# Main.net
KiCad netlist of a schematic drawn in Altium Designer
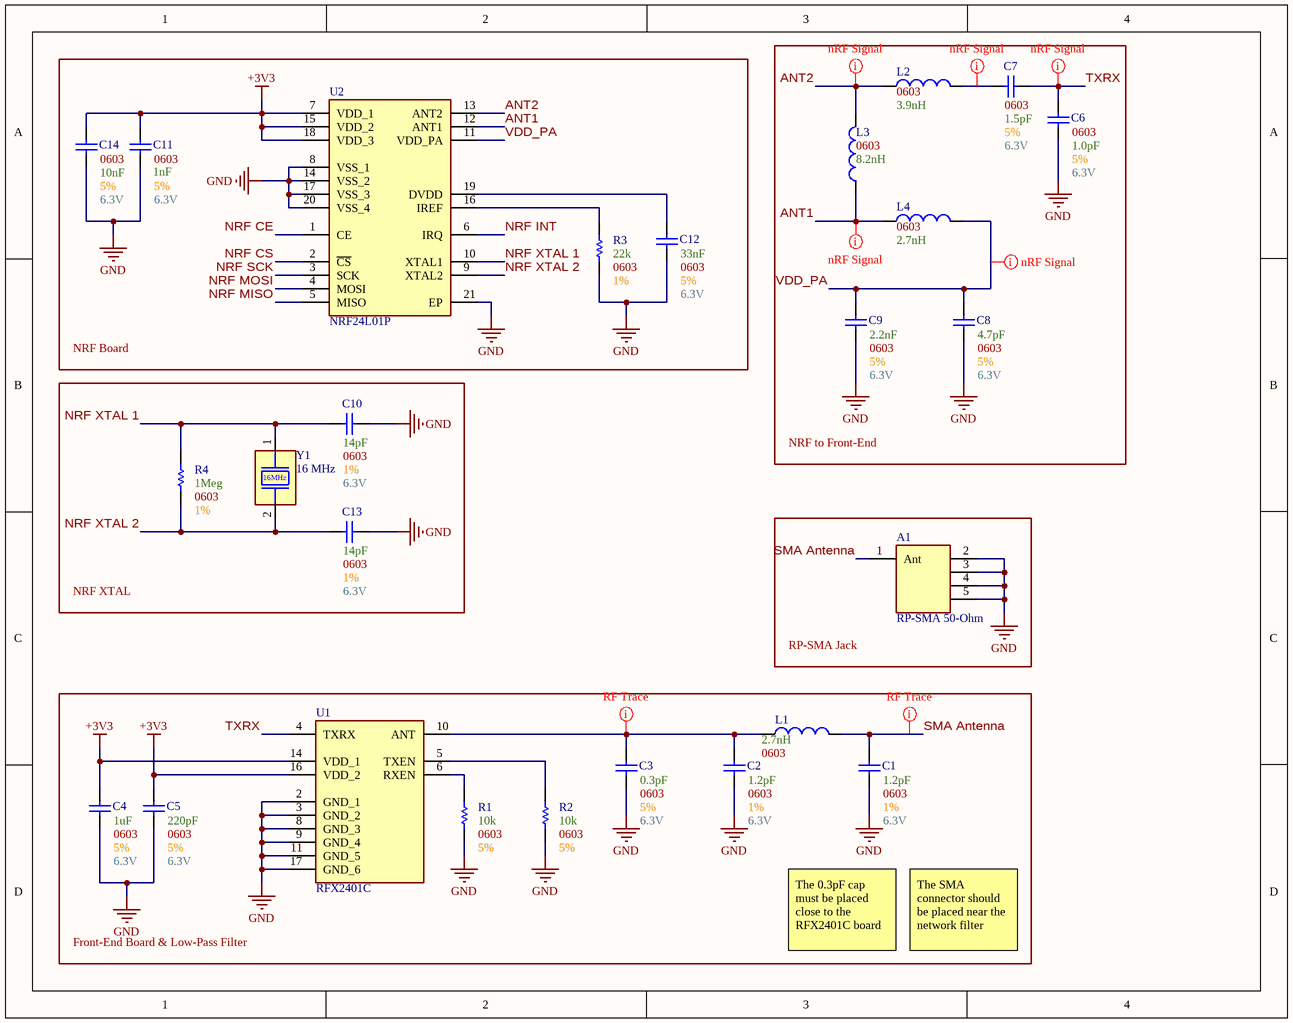
[diagram p0: Main.SchDoc]

(export (version "E")
  (design (tool "Eeschema 10.0.6"))
  (components
    (comp (ref "A1")
      (value "RP-SMA 50-Ohm")
      (footprint "[SMA] RP-SMA 90deg Jack")
      (description "PCB.RPSMAFRA.HT")
      (libsource (lib "RADM Connectors") (part "[SMA] RP-SMA 90deg Jack"))
    )
    (comp (ref "C1")
      (value "SMD Nonpolarized")
      (footprint "[Cap] SMD 0603")
      (fields
        (field (name "VOLTAGE") "6.3V")
        (field (name "TOLERANCE") "1%")
        (field (name "SIZE PACKAGE") "0603")
        (field (name "CAPACITANCE") "1.2pF")
      )
      (libsource (lib "RADM Components") (part "[Cap] SMD Nonpolarized"))
    )
    (comp (ref "C2")
      (value "SMD Nonpolarized")
      (footprint "[Cap] SMD 0603")
      (fields
        (field (name "VOLTAGE") "6.3V")
        (field (name "TOLERANCE") "1%")
        (field (name "SIZE PACKAGE") "0603")
        (field (name "CAPACITANCE") "1.2pF")
      )
      (libsource (lib "RADM Components") (part "[Cap] SMD Nonpolarized"))
    )
    (comp (ref "C3")
      (value "SMD Nonpolarized")
      (footprint "[Cap] SMD 0603")
      (fields
        (field (name "TOLERANCE") "5%")
        (field (name "SIZE PACKAGE") "0603")
        (field (name "CAPACITANCE") "0.3pF")
        (field (name "VOLTAGE") "6.3V")
      )
      (libsource (lib "RADM Components") (part "[Cap] SMD Nonpolarized"))
    )
    (comp (ref "C4")
      (value "SMD Nonpolarized")
      (footprint "[Cap] SMD 0603")
      (fields
        (field (name "TOLERANCE") "5%")
        (field (name "SIZE PACKAGE") "0603")
        (field (name "CAPACITANCE") "1uF")
        (field (name "VOLTAGE") "6.3V")
      )
      (libsource (lib "RADM Components") (part "[Cap] SMD Nonpolarized"))
    )
    (comp (ref "C5")
      (value "SMD Nonpolarized")
      (footprint "[Cap] SMD 0603")
      (fields
        (field (name "TOLERANCE") "5%")
        (field (name "SIZE PACKAGE") "0603")
        (field (name "CAPACITANCE") "220pF")
        (field (name "VOLTAGE") "6.3V")
      )
      (libsource (lib "RADM Components") (part "[Cap] SMD Nonpolarized"))
    )
    (comp (ref "C6")
      (value "SMD Nonpolarized")
      (footprint "[Cap] SMD 0603")
      (fields
        (field (name "TOLERANCE") "5%")
        (field (name "SIZE PACKAGE") "0603")
        (field (name "CAPACITANCE") "1.0pF")
        (field (name "VOLTAGE") "6.3V")
      )
      (libsource (lib "RADM Components") (part "[Cap] SMD Nonpolarized"))
    )
    (comp (ref "C7")
      (value "SMD Nonpolarized")
      (footprint "[Cap] SMD 0603")
      (fields
        (field (name "TOLERANCE") "5%")
        (field (name "SIZE PACKAGE") "0603")
        (field (name "CAPACITANCE") "1.5pF")
        (field (name "VOLTAGE") "6.3V")
      )
      (libsource (lib "RADM Components") (part "[Cap] SMD Nonpolarized"))
    )
    (comp (ref "C8")
      (value "SMD Nonpolarized")
      (footprint "[Cap] SMD 0603")
      (fields
        (field (name "TOLERANCE") "5%")
        (field (name "SIZE PACKAGE") "0603")
        (field (name "CAPACITANCE") "4.7pF")
        (field (name "VOLTAGE") "6.3V")
      )
      (libsource (lib "RADM Components") (part "[Cap] SMD Nonpolarized"))
    )
    (comp (ref "C9")
      (value "SMD Nonpolarized")
      (footprint "[Cap] SMD 0603")
      (fields
        (field (name "TOLERANCE") "5%")
        (field (name "SIZE PACKAGE") "0603")
        (field (name "CAPACITANCE") "2.2nF")
        (field (name "VOLTAGE") "6.3V")
      )
      (libsource (lib "RADM Components") (part "[Cap] SMD Nonpolarized"))
    )
    (comp (ref "C10")
      (value "SMD Nonpolarized")
      (footprint "[Cap] SMD 0603")
      (fields
        (field (name "TOLERANCE") "1%")
        (field (name "SIZE PACKAGE") "0603")
        (field (name "CAPACITANCE") "14pF")
        (field (name "VOLTAGE") "6.3V")
      )
      (libsource (lib "RADM Components") (part "[Cap] SMD Nonpolarized"))
    )
    (comp (ref "C11")
      (value "SMD Nonpolarized")
      (footprint "[Cap] SMD 0603")
      (fields
        (field (name "TOLERANCE") "5%")
        (field (name "SIZE PACKAGE") "0603")
        (field (name "CAPACITANCE") "1nF")
        (field (name "VOLTAGE") "6.3V")
      )
      (libsource (lib "RADM Components") (part "[Cap] SMD Nonpolarized"))
    )
    (comp (ref "C12")
      (value "SMD Nonpolarized")
      (footprint "[Cap] SMD 0603")
      (fields
        (field (name "TOLERANCE") "5%")
        (field (name "SIZE PACKAGE") "0603")
        (field (name "CAPACITANCE") "33nF")
        (field (name "VOLTAGE") "6.3V")
      )
      (libsource (lib "RADM Components") (part "[Cap] SMD Nonpolarized"))
    )
    (comp (ref "C13")
      (value "SMD Nonpolarized")
      (footprint "[Cap] SMD 0603")
      (fields
        (field (name "TOLERANCE") "1%")
        (field (name "SIZE PACKAGE") "0603")
        (field (name "CAPACITANCE") "14pF")
        (field (name "VOLTAGE") "6.3V")
      )
      (libsource (lib "RADM Components") (part "[Cap] SMD Nonpolarized"))
    )
    (comp (ref "C14")
      (value "SMD Nonpolarized")
      (footprint "[Cap] SMD 0603")
      (fields
        (field (name "TOLERANCE") "5%")
        (field (name "SIZE PACKAGE") "0603")
        (field (name "CAPACITANCE") "10nF")
        (field (name "VOLTAGE") "6.3V")
      )
      (libsource (lib "RADM Components") (part "[Cap] SMD Nonpolarized"))
    )
    (comp (ref "L1")
      (value "SMD Inductor")
      (footprint "[Inductor] SMD 0603")
      (fields (field (name "SIZE PACKAGE") "0603") (field (name "INDUCTANCE") "2.7nH"))
      (libsource (lib "RADM Components") (part "[Inductor] SMD Inductor"))
    )
    (comp (ref "L2")
      (value "SMD Inductor")
      (footprint "[Inductor] SMD 0603")
      (fields (field (name "SIZE PACKAGE") "0603") (field (name "INDUCTANCE") "3.9nH"))
      (libsource (lib "RADM Components") (part "[Inductor] SMD Inductor"))
    )
    (comp (ref "L3")
      (value "SMD Inductor")
      (footprint "[Inductor] SMD 0603")
      (fields (field (name "SIZE PACKAGE") "0603") (field (name "INDUCTANCE") "8.2nH"))
      (libsource (lib "RADM Components") (part "[Inductor] SMD Inductor"))
    )
    (comp (ref "L4")
      (value "SMD Inductor")
      (footprint "[Inductor] SMD 0603")
      (fields (field (name "SIZE PACKAGE") "0603") (field (name "INDUCTANCE") "2.7nH"))
      (libsource (lib "RADM Components") (part "[Inductor] SMD Inductor"))
    )
    (comp (ref "R1")
      (value "[Res] SMD Resistor")
      (footprint "[Res] SMD 0603")
      (description "Generic")
      (fields
        (field (name "TOLERANCE") "5%")
        (field (name "RESISTANCE") "10k")
        (field (name "SIZE PACKAGE") "0603")
      )
      (libsource (lib "RADM Components") (part "[Res] SMD Resistor"))
    )
    (comp (ref "R2")
      (value "[Res] SMD Resistor")
      (footprint "[Res] SMD 0603")
      (description "Generic")
      (fields
        (field (name "TOLERANCE") "5%")
        (field (name "RESISTANCE") "10k")
        (field (name "SIZE PACKAGE") "0603")
      )
      (libsource (lib "RADM Components") (part "[Res] SMD Resistor"))
    )
    (comp (ref "R3")
      (value "[Res] SMD Resistor")
      (footprint "[Res] SMD 0603")
      (description "Generic")
      (fields
        (field (name "TOLERANCE") "1%")
        (field (name "RESISTANCE") "22k")
        (field (name "SIZE PACKAGE") "0603")
      )
      (libsource (lib "RADM Components") (part "[Res] SMD Resistor"))
    )
    (comp (ref "R4")
      (value "[Res] SMD Resistor")
      (footprint "[Res] SMD 0603")
      (description "Generic")
      (fields
        (field (name "TOLERANCE") "1%")
        (field (name "RESISTANCE") "1Meg")
        (field (name "SIZE PACKAGE") "0603")
      )
      (libsource (lib "RADM Components") (part "[Res] SMD Resistor"))
    )
    (comp (ref "U1")
      (value "RFX2401C")
      (footprint "[IC] RF Front-End")
      (libsource (lib "RADM Components") (part "[IC] RF Front-End"))
    )
    (comp (ref "U2")
      (value "NRF24L01P")
      (footprint "[IC] NRF Transceiver")
      (description "NRF24L01P-R")
      (libsource (lib "RADM Components") (part "[IC] NRF Transceiver"))
    )
    (comp (ref "Y1")
      (value "16 MHz")
      (footprint "[XTAL] SMD 16MHz (2)")
      (description "ABM11-16.000MHZ-12-N1G-T")
      (libsource (lib "RADM Components") (part "[XTAL] SMD 16MHz (2)"))
    )
  )
  (nets
    (net (code "1") (name "+3V3") (class "Default")
      (node (ref "C11") (pin "2") (pinfunction "2_2") (pintype "passive"))
      (node (ref "C14") (pin "2") (pinfunction "2_2") (pintype "passive"))
      (node (ref "C4") (pin "2") (pinfunction "2_2") (pintype "passive"))
      (node (ref "C5") (pin "2") (pinfunction "2_2") (pintype "passive"))
      (node (ref "U1") (pin "14") (pinfunction "VDD_1_14") (pintype "passive"))
      (node (ref "U1") (pin "16") (pinfunction "VDD_2_16") (pintype "passive"))
      (node (ref "U2") (pin "15") (pinfunction "VDD_2_15") (pintype "passive"))
      (node (ref "U2") (pin "18") (pinfunction "VDD_3_18") (pintype "passive"))
      (node (ref "U2") (pin "7") (pinfunction "VDD_1_7") (pintype "passive"))
    )
    (net (code "2") (name "/ANT1") (class "Default")
      (node (ref "L3") (pin "1") (pinfunction "1_1") (pintype "passive"))
      (node (ref "L4") (pin "1") (pinfunction "1_1") (pintype "passive"))
      (node (ref "U2") (pin "12") (pinfunction "ANT1_12") (pintype "passive"))
    )
    (net (code "3") (name "/ANT2") (class "Default")
      (node (ref "L2") (pin "1") (pinfunction "1_1") (pintype "passive"))
      (node (ref "L3") (pin "2") (pinfunction "2_2") (pintype "passive"))
      (node (ref "U2") (pin "13") (pinfunction "ANT2_13") (pintype "passive"))
    )
    (net (code "4") (name "/NRF CE") (class "Default")
      (node (ref "U2") (pin "1") (pinfunction "CE_1") (pintype "passive"))
    )
    (net (code "5") (name "/NRF CS") (class "Default")
      (node (ref "U2") (pin "2") (pinfunction "CS_2") (pintype "passive"))
    )
    (net (code "6") (name "/NRF INT") (class "Default")
      (node (ref "U2") (pin "6") (pinfunction "IRQ_6") (pintype "passive"))
    )
    (net (code "7") (name "/NRF MISO") (class "Default")
      (node (ref "U2") (pin "5") (pinfunction "MISO_5") (pintype "passive"))
    )
    (net (code "8") (name "/NRF MOSI") (class "Default")
      (node (ref "U2") (pin "4") (pinfunction "MOSI_4") (pintype "passive"))
    )
    (net (code "9") (name "/NRF SCK") (class "Default")
      (node (ref "U2") (pin "3") (pinfunction "SCK_3") (pintype "passive"))
    )
    (net (code "10") (name "/NRF XTAL 1") (class "Default")
      (node (ref "C10") (pin "1") (pinfunction "1_1") (pintype "passive"))
      (node (ref "R4") (pin "1") (pinfunction "1_1") (pintype "passive"))
      (node (ref "U2") (pin "10") (pinfunction "XTAL1_10") (pintype "passive"))
      (node (ref "Y1") (pin "1") (pinfunction "XTAL1_1") (pintype "passive"))
    )
    (net (code "11") (name "/NRF XTAL 2") (class "Default")
      (node (ref "C13") (pin "1") (pinfunction "1_1") (pintype "passive"))
      (node (ref "R4") (pin "2") (pinfunction "2_2") (pintype "passive"))
      (node (ref "U2") (pin "9") (pinfunction "XTAL2_9") (pintype "passive"))
      (node (ref "Y1") (pin "2") (pinfunction "XTAL2_2") (pintype "passive"))
    )
    (net (code "12") (name "/SMA Antenna") (class "Default")
      (node (ref "A1") (pin "1") (pinfunction "Ant_1") (pintype "passive"))
      (node (ref "C1") (pin "2") (pinfunction "2_2") (pintype "passive"))
      (node (ref "L1") (pin "2") (pinfunction "2_2") (pintype "passive"))
    )
    (net (code "13") (name "/TXRX") (class "Default")
      (node (ref "C6") (pin "1") (pinfunction "1_1") (pintype "passive"))
      (node (ref "C7") (pin "1") (pinfunction "1_1") (pintype "passive"))
      (node (ref "U1") (pin "4") (pinfunction "TXRX_4") (pintype "passive"))
    )
    (net (code "14") (name "/VDD_PA") (class "Default")
      (node (ref "C8") (pin "2") (pinfunction "2_2") (pintype "passive"))
      (node (ref "C9") (pin "2") (pinfunction "2_2") (pintype "passive"))
      (node (ref "L4") (pin "2") (pinfunction "2_2") (pintype "passive"))
      (node (ref "U2") (pin "11") (pinfunction "VDD_PA_11") (pintype "passive"))
    )
    (net (code "15") (name "GND") (class "Default")
      (node (ref "A1") (pin "2") (pinfunction "2_2") (pintype "passive"))
      (node (ref "A1") (pin "3") (pinfunction "3_3") (pintype "passive"))
      (node (ref "A1") (pin "4") (pinfunction "4_4") (pintype "passive"))
      (node (ref "A1") (pin "5") (pinfunction "5_5") (pintype "passive"))
      (node (ref "C1") (pin "1") (pinfunction "1_1") (pintype "passive"))
      (node (ref "C10") (pin "2") (pinfunction "2_2") (pintype "passive"))
      (node (ref "C11") (pin "1") (pinfunction "1_1") (pintype "passive"))
      (node (ref "C12") (pin "1") (pinfunction "1_1") (pintype "passive"))
      (node (ref "C13") (pin "2") (pinfunction "2_2") (pintype "passive"))
      (node (ref "C14") (pin "1") (pinfunction "1_1") (pintype "passive"))
      (node (ref "C2") (pin "1") (pinfunction "1_1") (pintype "passive"))
      (node (ref "C3") (pin "1") (pinfunction "1_1") (pintype "passive"))
      (node (ref "C4") (pin "1") (pinfunction "1_1") (pintype "passive"))
      (node (ref "C5") (pin "1") (pinfunction "1_1") (pintype "passive"))
      (node (ref "C6") (pin "2") (pinfunction "2_2") (pintype "passive"))
      (node (ref "C8") (pin "1") (pinfunction "1_1") (pintype "passive"))
      (node (ref "C9") (pin "1") (pinfunction "1_1") (pintype "passive"))
      (node (ref "R1") (pin "1") (pinfunction "1_1") (pintype "passive"))
      (node (ref "R2") (pin "1") (pinfunction "1_1") (pintype "passive"))
      (node (ref "R3") (pin "1") (pinfunction "1_1") (pintype "passive"))
      (node (ref "U1") (pin "11") (pinfunction "GND_5_11") (pintype "passive"))
      (node (ref "U1") (pin "17") (pinfunction "GND_6_17") (pintype "passive"))
      (node (ref "U1") (pin "2") (pinfunction "GND_1_2") (pintype "passive"))
      (node (ref "U1") (pin "3") (pinfunction "GND_2_3") (pintype "passive"))
      (node (ref "U1") (pin "8") (pinfunction "GND_3_8") (pintype "passive"))
      (node (ref "U1") (pin "9") (pinfunction "GND_4_9") (pintype "passive"))
      (node (ref "U2") (pin "14") (pinfunction "VSS_2_14") (pintype "passive"))
      (node (ref "U2") (pin "17") (pinfunction "VSS_3_17") (pintype "passive"))
      (node (ref "U2") (pin "20") (pinfunction "VSS_4_20") (pintype "passive"))
      (node (ref "U2") (pin "21") (pinfunction "EP_21") (pintype "passive"))
      (node (ref "U2") (pin "8") (pinfunction "VSS_1_8") (pintype "passive"))
    )
    (net (code "16") (name "Net-(C7-Pad2)") (class "Default")
      (node (ref "C7") (pin "2") (pinfunction "2_2") (pintype "passive"))
      (node (ref "L2") (pin "2") (pinfunction "2_2") (pintype "passive"))
    )
    (net (code "17") (name "Net-(U1-ANT)") (class "Default")
      (node (ref "C2") (pin "2") (pinfunction "2_2") (pintype "passive"))
      (node (ref "C3") (pin "2") (pinfunction "2_2") (pintype "passive"))
      (node (ref "L1") (pin "1") (pinfunction "1_1") (pintype "passive"))
      (node (ref "U1") (pin "10") (pinfunction "ANT_10") (pintype "passive"))
    )
    (net (code "18") (name "Net-(U1-RXEN)") (class "Default")
      (node (ref "R1") (pin "2") (pinfunction "2_2") (pintype "passive"))
      (node (ref "U1") (pin "6") (pinfunction "RXEN_6") (pintype "passive"))
    )
    (net (code "19") (name "Net-(U1-TXEN)") (class "Default")
      (node (ref "R2") (pin "2") (pinfunction "2_2") (pintype "passive"))
      (node (ref "U1") (pin "5") (pinfunction "TXEN_5") (pintype "passive"))
    )
    (net (code "20") (name "Net-(U2-DVDD)") (class "Default")
      (node (ref "C12") (pin "2") (pinfunction "2_2") (pintype "passive"))
      (node (ref "U2") (pin "19") (pinfunction "DVDD_19") (pintype "passive"))
    )
    (net (code "21") (name "Net-(U2-IREF)") (class "Default")
      (node (ref "R3") (pin "2") (pinfunction "2_2") (pintype "passive"))
      (node (ref "U2") (pin "16") (pinfunction "IREF_16") (pintype "passive"))
    )
  )
)
